# CV060_AO.net
KiCad netlist of a schematic drawn in Altium Designer
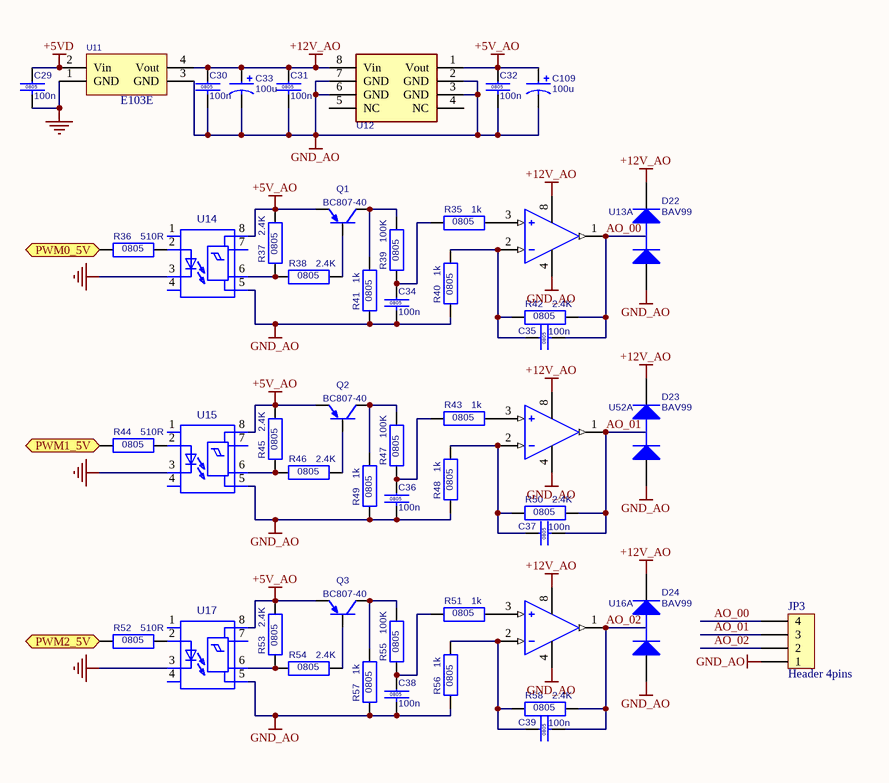
[diagram p0: CV060_AO.SchDoc]

(export (version "E")
  (design (tool "Eeschema 10.0.6"))
  (components
    (comp (ref "C29")
      (value "100n")
      (footprint "RC0805")
      (description "Chip capacitor, 20p")
      (fields
        (field (name "VOLTAGE") "50V")
        (field (name "MANUFACTURER") "KEMET, YAGEO")
        (field (name "CASE") "0805")
        (field (name "PUBLISHER") "ppavlov")
      )
      (libsource (lib "Aldiva_Altium_Library") (part "Capacitor_nonpolar_case"))
    )
    (comp (ref "C30")
      (value "100n")
      (footprint "RC0805")
      (description "Chip capacitor, 20p")
      (fields
        (field (name "VOLTAGE") "50V")
        (field (name "MANUFACTURER") "KEMET, YAGEO")
        (field (name "CASE") "0805")
        (field (name "PUBLISHER") "ppavlov")
      )
      (libsource (lib "Aldiva_Altium_Library") (part "Capacitor_nonpolar_case"))
    )
    (comp (ref "C31")
      (value "100n")
      (footprint "RC0805")
      (description "Chip capacitor, 20p")
      (fields
        (field (name "VOLTAGE") "50V")
        (field (name "MANUFACTURER") "KEMET, YAGEO")
        (field (name "CASE") "0805")
        (field (name "PUBLISHER") "ppavlov")
      )
      (libsource (lib "Aldiva_Altium_Library") (part "Capacitor_nonpolar_case"))
    )
    (comp (ref "C32")
      (value "100n")
      (footprint "RC0805")
      (description "Chip capacitor, 20p")
      (fields
        (field (name "VOLTAGE") "50V")
        (field (name "MANUFACTURER") "KEMET, YAGEO")
        (field (name "CASE") "0805")
        (field (name "PUBLISHER") "ppavlov")
      )
      (libsource (lib "Aldiva_Altium_Library") (part "Capacitor_nonpolar_case"))
    )
    (comp (ref "C33")
      (value "100u")
      (footprint "CEH12.5D5P2.5")
      (description "Electrolytic capacitor")
      (fields
        (field (name "PART NUMBER") "CEH12.5D5P2.5M-16V-100U")
        (field (name "VOLTAGE") "16V")
        (field (name "PUBLISHER") "ppavlov")
      )
      (libsource (lib "Aldiva_Altium_Library") (part "Capacitor_polar"))
    )
    (comp (ref "C34")
      (value "100n")
      (footprint "RC0805")
      (description "Chip capacitor, 20p")
      (fields
        (field (name "VOLTAGE") "50V")
        (field (name "MANUFACTURER") "KEMET, YAGEO")
        (field (name "CASE") "0805")
        (field (name "PUBLISHER") "ppavlov")
      )
      (libsource (lib "Aldiva_Altium_Library") (part "Capacitor_nonpolar_case"))
    )
    (comp (ref "C35")
      (value "100n")
      (footprint "RC0805")
      (description "Chip capacitor, 20p")
      (fields
        (field (name "VOLTAGE") "50V")
        (field (name "MANUFACTURER") "KEMET, YAGEO")
        (field (name "CASE") "0805")
        (field (name "PUBLISHER") "ppavlov")
      )
      (libsource (lib "Aldiva_Altium_Library") (part "Capacitor_nonpolar_case"))
    )
    (comp (ref "C36")
      (value "100n")
      (footprint "RC0805")
      (description "Chip capacitor, 20p")
      (fields
        (field (name "VOLTAGE") "50V")
        (field (name "MANUFACTURER") "KEMET, YAGEO")
        (field (name "CASE") "0805")
        (field (name "PUBLISHER") "ppavlov")
      )
      (libsource (lib "Aldiva_Altium_Library") (part "Capacitor_nonpolar_case"))
    )
    (comp (ref "C37")
      (value "100n")
      (footprint "RC0805")
      (description "Chip capacitor, 20p")
      (fields
        (field (name "VOLTAGE") "50V")
        (field (name "MANUFACTURER") "KEMET, YAGEO")
        (field (name "CASE") "0805")
        (field (name "PUBLISHER") "ppavlov")
      )
      (libsource (lib "Aldiva_Altium_Library") (part "Capacitor_nonpolar_case"))
    )
    (comp (ref "C38")
      (value "100n")
      (footprint "RC0805")
      (description "Chip capacitor, 20p")
      (fields
        (field (name "VOLTAGE") "50V")
        (field (name "MANUFACTURER") "KEMET, YAGEO")
        (field (name "CASE") "0805")
        (field (name "PUBLISHER") "ppavlov")
      )
      (libsource (lib "Aldiva_Altium_Library") (part "Capacitor_nonpolar_case"))
    )
    (comp (ref "C39")
      (value "100n")
      (footprint "RC0805")
      (description "Chip capacitor, 20p")
      (fields
        (field (name "VOLTAGE") "50V")
        (field (name "MANUFACTURER") "KEMET, YAGEO")
        (field (name "CASE") "0805")
        (field (name "PUBLISHER") "ppavlov")
      )
      (libsource (lib "Aldiva_Altium_Library") (part "Capacitor_nonpolar_case"))
    )
    (comp (ref "C109")
      (value "100u")
      (footprint "CEH12.5D5P2.5")
      (description "Electrolytic capacitor")
      (fields
        (field (name "PART NUMBER") "CEH12.5D5P2.5M-16V-100U")
        (field (name "VOLTAGE") "16V")
        (field (name "PUBLISHER") "ppavlov")
      )
      (libsource (lib "Aldiva_Altium_Library") (part "Capacitor_polar"))
    )
    (comp (ref "D22")
      (value "BAV99")
      (footprint "SOT23-3")
      (description "Dual small signal diode")
      (fields
        (field (name "MANUFACTURER") "Fairchild")
        (field (name "PART NUMBER") "BAV99")
        (field (name "VOLTAGE") "70V")
        (field (name "PUBLISHER") "tkondratyuk")
      )
      (libsource (lib "Aldiva_Altium_Library") (part "BAV99"))
    )
    (comp (ref "D23")
      (value "BAV99")
      (footprint "SOT23-3")
      (description "Dual small signal diode")
      (fields
        (field (name "MANUFACTURER") "Fairchild")
        (field (name "PART NUMBER") "BAV99")
        (field (name "VOLTAGE") "70V")
        (field (name "PUBLISHER") "tkondratyuk")
      )
      (libsource (lib "Aldiva_Altium_Library") (part "BAV99"))
    )
    (comp (ref "D24")
      (value "BAV99")
      (footprint "SOT23-3")
      (description "Dual small signal diode")
      (fields
        (field (name "MANUFACTURER") "Fairchild")
        (field (name "PART NUMBER") "BAV99")
        (field (name "VOLTAGE") "70V")
        (field (name "PUBLISHER") "tkondratyuk")
      )
      (libsource (lib "Aldiva_Altium_Library") (part "BAV99"))
    )
    (comp (ref "JP3")
      (value "Header 4pins")
      (footprint "PHOENIX_5.08_4PINS")
      (description "5.08mm angled 4pins receptabe")
      (fields
        (field (name "PART NUMBER") "2EDGR-5.08-04P-14")
        (field (name "MANUFACTURER PART NUMBER") "2EDGR-5.0-04P-14")
        (field (name "PUBLISHER") "ppavlov")
      )
      (libsource (lib "Aldiva_Altium_Library") (part "Header 4pins"))
    )
    (comp (ref "Q1")
      (value "PNP_transistor_SOT23-3")
      (footprint "SOT23-3")
      (description "General Purpose  PNP Transistor")
      (fields
        (field (name "PART NUMBER") "BC807-40")
        (field (name "MANUFACTURER") "ONS, NXP")
        (field (name "MANUFACTURER PART NUMBER") "BC807?40LT1G")
        (field (name "PUBLISHER") "tkondratyuk")
      )
      (libsource (lib "Aldiva_Altium_Library") (part "PNP_transistor_SOT23-3"))
    )
    (comp (ref "Q2")
      (value "PNP_transistor_SOT23-3")
      (footprint "SOT23-3")
      (description "General Purpose  PNP Transistor")
      (fields
        (field (name "PART NUMBER") "BC807-40")
        (field (name "MANUFACTURER") "ONS, NXP")
        (field (name "MANUFACTURER PART NUMBER") "BC807?40LT1G")
        (field (name "PUBLISHER") "tkondratyuk")
      )
      (libsource (lib "Aldiva_Altium_Library") (part "PNP_transistor_SOT23-3"))
    )
    (comp (ref "Q3")
      (value "PNP_transistor_SOT23-3")
      (footprint "SOT23-3")
      (description "General Purpose  PNP Transistor")
      (fields
        (field (name "PART NUMBER") "BC807-40")
        (field (name "MANUFACTURER") "ONS, NXP")
        (field (name "MANUFACTURER PART NUMBER") "BC807?40LT1G")
        (field (name "PUBLISHER") "tkondratyuk")
      )
      (libsource (lib "Aldiva_Altium_Library") (part "PNP_transistor_SOT23-3"))
    )
    (comp (ref "R35")
      (value "1k")
      (footprint "RC0805")
      (description "Chip resistor")
      (fields
        (field (name "CASE") "0805")
        (field (name "PART NUMBER") "RC0805F-1K00")
        (field (name "VOLTAGE") "200V")
        (field (name "PUBLISHER") "ppavlov")
      )
      (libsource (lib "Aldiva_Altium_Library") (part "Resistor"))
    )
    (comp (ref "R36")
      (value "510R")
      (footprint "RC0805")
      (description "Chip resistor")
      (fields
        (field (name "CASE") "0805")
        (field (name "PART NUMBER") "RC0805F-510R")
        (field (name "VOLTAGE") "200V")
        (field (name "PUBLISHER") "ppavlov")
      )
      (libsource (lib "Aldiva_Altium_Library") (part "Resistor"))
    )
    (comp (ref "R37")
      (value "2.4K")
      (footprint "RC0805")
      (description "Chip resistor")
      (fields
        (field (name "CASE") "0805")
        (field (name "PART NUMBER") "RC0805F-2K40")
        (field (name "VOLTAGE") "200V")
        (field (name "PUBLISHER") "ppavlov")
      )
      (libsource (lib "Aldiva_Altium_Library") (part "Resistor"))
    )
    (comp (ref "R38")
      (value "2.4K")
      (footprint "RC0805")
      (description "Chip resistor")
      (fields
        (field (name "CASE") "0805")
        (field (name "PART NUMBER") "RC0805F-2K40")
        (field (name "VOLTAGE") "200V")
        (field (name "PUBLISHER") "ppavlov")
      )
      (libsource (lib "Aldiva_Altium_Library") (part "Resistor"))
    )
    (comp (ref "R39")
      (value "100K")
      (footprint "RC0805")
      (description "Chip resistor")
      (fields
        (field (name "CASE") "0805")
        (field (name "PART NUMBER") "RC0805F-100K")
        (field (name "VOLTAGE") "200V")
        (field (name "PUBLISHER") "ppavlov")
      )
      (libsource (lib "Aldiva_Altium_Library") (part "Resistor"))
    )
    (comp (ref "R40")
      (value "1k")
      (footprint "RC0805")
      (description "Chip resistor")
      (fields
        (field (name "CASE") "0805")
        (field (name "PART NUMBER") "RC0805F-1K00")
        (field (name "VOLTAGE") "200V")
        (field (name "PUBLISHER") "ppavlov")
      )
      (libsource (lib "Aldiva_Altium_Library") (part "Resistor"))
    )
    (comp (ref "R41")
      (value "1k")
      (footprint "RC0805")
      (description "Chip resistor")
      (fields
        (field (name "CASE") "0805")
        (field (name "PART NUMBER") "RC0805F-1K00")
        (field (name "VOLTAGE") "200V")
        (field (name "PUBLISHER") "ppavlov")
      )
      (libsource (lib "Aldiva_Altium_Library") (part "Resistor"))
    )
    (comp (ref "R42")
      (value "2.4K")
      (footprint "RC0805")
      (description "Chip resistor")
      (fields
        (field (name "CASE") "0805")
        (field (name "PART NUMBER") "RC0805F-2K40")
        (field (name "VOLTAGE") "200V")
        (field (name "PUBLISHER") "ppavlov")
      )
      (libsource (lib "Aldiva_Altium_Library") (part "Resistor"))
    )
    (comp (ref "R43")
      (value "1k")
      (footprint "RC0805")
      (description "Chip resistor")
      (fields
        (field (name "CASE") "0805")
        (field (name "PART NUMBER") "RC0805F-1K00")
        (field (name "VOLTAGE") "200V")
        (field (name "PUBLISHER") "ppavlov")
      )
      (libsource (lib "Aldiva_Altium_Library") (part "Resistor"))
    )
    (comp (ref "R44")
      (value "510R")
      (footprint "RC0805")
      (description "Chip resistor")
      (fields
        (field (name "CASE") "0805")
        (field (name "PART NUMBER") "RC0805F-510R")
        (field (name "VOLTAGE") "200V")
        (field (name "PUBLISHER") "ppavlov")
      )
      (libsource (lib "Aldiva_Altium_Library") (part "Resistor"))
    )
    (comp (ref "R45")
      (value "2.4K")
      (footprint "RC0805")
      (description "Chip resistor")
      (fields
        (field (name "CASE") "0805")
        (field (name "PART NUMBER") "RC0805F-2K40")
        (field (name "VOLTAGE") "200V")
        (field (name "PUBLISHER") "ppavlov")
      )
      (libsource (lib "Aldiva_Altium_Library") (part "Resistor"))
    )
    (comp (ref "R46")
      (value "2.4K")
      (footprint "RC0805")
      (description "Chip resistor")
      (fields
        (field (name "CASE") "0805")
        (field (name "PART NUMBER") "RC0805F-2K40")
        (field (name "VOLTAGE") "200V")
        (field (name "PUBLISHER") "ppavlov")
      )
      (libsource (lib "Aldiva_Altium_Library") (part "Resistor"))
    )
    (comp (ref "R47")
      (value "100K")
      (footprint "RC0805")
      (description "Chip resistor")
      (fields
        (field (name "CASE") "0805")
        (field (name "PART NUMBER") "RC0805F-100K")
        (field (name "VOLTAGE") "200V")
        (field (name "PUBLISHER") "ppavlov")
      )
      (libsource (lib "Aldiva_Altium_Library") (part "Resistor"))
    )
    (comp (ref "R48")
      (value "1k")
      (footprint "RC0805")
      (description "Chip resistor")
      (fields
        (field (name "CASE") "0805")
        (field (name "PART NUMBER") "RC0805F-1K00")
        (field (name "VOLTAGE") "200V")
        (field (name "PUBLISHER") "ppavlov")
      )
      (libsource (lib "Aldiva_Altium_Library") (part "Resistor"))
    )
    (comp (ref "R49")
      (value "1k")
      (footprint "RC0805")
      (description "Chip resistor")
      (fields
        (field (name "CASE") "0805")
        (field (name "PART NUMBER") "RC0805F-1K00")
        (field (name "VOLTAGE") "200V")
        (field (name "PUBLISHER") "ppavlov")
      )
      (libsource (lib "Aldiva_Altium_Library") (part "Resistor"))
    )
    (comp (ref "R50")
      (value "2.4K")
      (footprint "RC0805")
      (description "Chip resistor")
      (fields
        (field (name "CASE") "0805")
        (field (name "PART NUMBER") "RC0805F-2K40")
        (field (name "VOLTAGE") "200V")
        (field (name "PUBLISHER") "ppavlov")
      )
      (libsource (lib "Aldiva_Altium_Library") (part "Resistor"))
    )
    (comp (ref "R51")
      (value "1k")
      (footprint "RC0805")
      (description "Chip resistor")
      (fields
        (field (name "CASE") "0805")
        (field (name "PART NUMBER") "RC0805F-1K00")
        (field (name "VOLTAGE") "200V")
        (field (name "PUBLISHER") "ppavlov")
      )
      (libsource (lib "Aldiva_Altium_Library") (part "Resistor"))
    )
    (comp (ref "R52")
      (value "510R")
      (footprint "RC0805")
      (description "Chip resistor")
      (fields
        (field (name "CASE") "0805")
        (field (name "PART NUMBER") "RC0805F-510R")
        (field (name "VOLTAGE") "200V")
        (field (name "PUBLISHER") "ppavlov")
      )
      (libsource (lib "Aldiva_Altium_Library") (part "Resistor"))
    )
    (comp (ref "R53")
      (value "2.4K")
      (footprint "RC0805")
      (description "Chip resistor")
      (fields
        (field (name "CASE") "0805")
        (field (name "PART NUMBER") "RC0805F-2K40")
        (field (name "VOLTAGE") "200V")
        (field (name "PUBLISHER") "ppavlov")
      )
      (libsource (lib "Aldiva_Altium_Library") (part "Resistor"))
    )
    (comp (ref "R54")
      (value "2.4K")
      (footprint "RC0805")
      (description "Chip resistor")
      (fields
        (field (name "CASE") "0805")
        (field (name "PART NUMBER") "RC0805F-2K40")
        (field (name "VOLTAGE") "200V")
        (field (name "PUBLISHER") "ppavlov")
      )
      (libsource (lib "Aldiva_Altium_Library") (part "Resistor"))
    )
    (comp (ref "R55")
      (value "100K")
      (footprint "RC0805")
      (description "Chip resistor")
      (fields
        (field (name "CASE") "0805")
        (field (name "PART NUMBER") "RC0805F-100K")
        (field (name "VOLTAGE") "200V")
        (field (name "PUBLISHER") "ppavlov")
      )
      (libsource (lib "Aldiva_Altium_Library") (part "Resistor"))
    )
    (comp (ref "R56")
      (value "1k")
      (footprint "RC0805")
      (description "Chip resistor")
      (fields
        (field (name "CASE") "0805")
        (field (name "PART NUMBER") "RC0805F-1K00")
        (field (name "VOLTAGE") "200V")
        (field (name "PUBLISHER") "ppavlov")
      )
      (libsource (lib "Aldiva_Altium_Library") (part "Resistor"))
    )
    (comp (ref "R57")
      (value "1k")
      (footprint "RC0805")
      (description "Chip resistor")
      (fields
        (field (name "CASE") "0805")
        (field (name "PART NUMBER") "RC0805F-1K00")
        (field (name "VOLTAGE") "200V")
        (field (name "PUBLISHER") "ppavlov")
      )
      (libsource (lib "Aldiva_Altium_Library") (part "Resistor"))
    )
    (comp (ref "R58")
      (value "2.4K")
      (footprint "RC0805")
      (description "Chip resistor")
      (fields
        (field (name "CASE") "0805")
        (field (name "PART NUMBER") "RC0805F-2K40")
        (field (name "VOLTAGE") "200V")
        (field (name "PUBLISHER") "ppavlov")
      )
      (libsource (lib "Aldiva_Altium_Library") (part "Resistor"))
    )
    (comp (ref "U11")
      (value "~")
      (footprint "SIP4")
      (description "1W Insulated DCDC converter 5 to 12V")
      (fields
        (field (name "PART NUMBER") "1-05-12S")
        (field (name "MANUFACTURER") "TI")
        (field (name "MANUFACTURER PART NUMBER") "E103E")
        (field (name "PUBLISHER") "ppavlov")
      )
      (libsource (lib "Aldiva_Altium_Library") (part "DCDC"))
    )
    (comp (ref "U12")
      (value "L78L05CD")
      (footprint "SO-8")
      (description "Regulator 100ma 5V")
      (fields (field (name "MANUFACTURER") "ST") (field (name "PUBLISHER") "ppavlov"))
      (libsource (lib "Aldiva_Altium_Library") (part "78L05"))
    )
    (comp (ref "U13")
      (value "LM2904D")
      (footprint "SO-8")
      (description "Dual opamps")
      (fields (field (name "MANUFACTURER") "TI") (field (name "PUBLISHER") "tkondratyuk"))
      (libsource (lib "Aldiva_Altium_Library") (part "LM2904D"))
    )
    (comp (ref "U14")
      (value "6N137")
      (footprint "DIP8")
      (description "High CMR, High Speed TTL\r\nCompatible Optocouplers")
      (fields (field (name "PUBLISHER") "ppavlov"))
      (libsource (lib "Aldiva_Altium_Library") (part "6N137"))
    )
    (comp (ref "U15")
      (value "6N137")
      (footprint "DIP8")
      (description "High CMR, High Speed TTL\r\nCompatible Optocouplers")
      (fields (field (name "PUBLISHER") "ppavlov"))
      (libsource (lib "Aldiva_Altium_Library") (part "6N137"))
    )
    (comp (ref "U16")
      (value "LM2904D")
      (footprint "SO-8")
      (description "Dual opamps")
      (fields (field (name "MANUFACTURER") "TI") (field (name "PUBLISHER") "tkondratyuk"))
      (libsource (lib "Aldiva_Altium_Library") (part "LM2904D"))
    )
    (comp (ref "U17")
      (value "6N137")
      (footprint "DIP8")
      (description "High CMR, High Speed TTL\r\nCompatible Optocouplers")
      (fields (field (name "PUBLISHER") "ppavlov"))
      (libsource (lib "Aldiva_Altium_Library") (part "6N137"))
    )
    (comp (ref "U52")
      (value "LM2904D")
      (footprint "SO-8")
      (description "Dual opamps")
      (fields (field (name "MANUFACTURER") "TI") (field (name "PUBLISHER") "tkondratyuk"))
      (libsource (lib "Aldiva_Altium_Library") (part "LM2904D"))
    )
  )
  (nets
    (net (code "1") (name "+5VD") (class "Default")
      (node (ref "C29") (pin "1") (pinfunction "1_1") (pintype "passive"))
      (node (ref "U11") (pin "2") (pinfunction "Vin_2") (pintype "passive"))
    )
    (net (code "2") (name "+5V_AO") (class "Default")
      (node (ref "C109") (pin "1") (pinfunction "1_1") (pintype "passive"))
      (node (ref "C32") (pin "1") (pinfunction "1_1") (pintype "passive"))
      (node (ref "Q1") (pin "2") (pinfunction "E_2") (pintype "passive"))
      (node (ref "Q2") (pin "2") (pinfunction "E_2") (pintype "passive"))
      (node (ref "Q3") (pin "2") (pinfunction "E_2") (pintype "passive"))
      (node (ref "R37") (pin "2") (pinfunction "2_2") (pintype "passive"))
      (node (ref "R45") (pin "2") (pinfunction "2_2") (pintype "passive"))
      (node (ref "R53") (pin "2") (pinfunction "2_2") (pintype "passive"))
      (node (ref "U12") (pin "1") (pinfunction "Vout_1") (pintype "passive"))
      (node (ref "U14") (pin "8") (pintype "passive"))
      (node (ref "U15") (pin "8") (pintype "passive"))
      (node (ref "U17") (pin "8") (pintype "passive"))
    )
    (net (code "3") (name "+12V_AO") (class "Default")
      (node (ref "C30") (pin "1") (pinfunction "1_1") (pintype "passive"))
      (node (ref "C31") (pin "1") (pinfunction "1_1") (pintype "passive"))
      (node (ref "C33") (pin "1") (pinfunction "1_1") (pintype "passive"))
      (node (ref "D22") (pin "2") (pinfunction "K_2") (pintype "passive"))
      (node (ref "D23") (pin "2") (pinfunction "K_2") (pintype "passive"))
      (node (ref "D24") (pin "2") (pinfunction "K_2") (pintype "passive"))
      (node (ref "U11") (pin "4") (pinfunction "Vout_4") (pintype "passive"))
      (node (ref "U12") (pin "8") (pinfunction "Vin_8") (pintype "passive"))
      (node (ref "U13") (pin "8") (pinfunction "Vcc+_8") (pintype "power_in"))
      (node (ref "U16") (pin "8") (pinfunction "Vcc+_8") (pintype "power_in"))
      (node (ref "U52") (pin "8") (pinfunction "Vcc+_8") (pintype "power_in"))
    )
    (net (code "4") (name "/AO_00") (class "Default")
      (node (ref "C35") (pin "2") (pinfunction "2_2") (pintype "passive"))
      (node (ref "D22") (pin "3") (pinfunction "C_3") (pintype "passive"))
      (node (ref "JP3") (pin "4") (pinfunction "4_4") (pintype "passive"))
      (node (ref "R42") (pin "2") (pinfunction "2_2") (pintype "passive"))
      (node (ref "U13") (pin "1") (pinfunction "OUT1_1") (pintype "output"))
    )
    (net (code "5") (name "/AO_01") (class "Default")
      (node (ref "C37") (pin "2") (pinfunction "2_2") (pintype "passive"))
      (node (ref "D23") (pin "3") (pinfunction "C_3") (pintype "passive"))
      (node (ref "JP3") (pin "3") (pinfunction "3_3") (pintype "passive"))
      (node (ref "R50") (pin "2") (pinfunction "2_2") (pintype "passive"))
      (node (ref "U52") (pin "1") (pinfunction "OUT1_1") (pintype "output"))
    )
    (net (code "6") (name "/AO_02") (class "Default")
      (node (ref "C39") (pin "2") (pinfunction "2_2") (pintype "passive"))
      (node (ref "D24") (pin "3") (pinfunction "C_3") (pintype "passive"))
      (node (ref "JP3") (pin "2") (pinfunction "2_2") (pintype "passive"))
      (node (ref "R58") (pin "2") (pinfunction "2_2") (pintype "passive"))
      (node (ref "U16") (pin "1") (pinfunction "OUT1_1") (pintype "output"))
    )
    (net (code "7") (name "/PWM0_5V") (class "Default")
      (node (ref "R36") (pin "1") (pinfunction "1_1") (pintype "passive"))
    )
    (net (code "8") (name "/PWM1_5V") (class "Default")
      (node (ref "R44") (pin "1") (pinfunction "1_1") (pintype "passive"))
    )
    (net (code "9") (name "/PWM2_5V") (class "Default")
      (node (ref "R52") (pin "1") (pinfunction "1_1") (pintype "passive"))
    )
    (net (code "10") (name "DGND") (class "Default")
      (node (ref "C29") (pin "2") (pinfunction "2_2") (pintype "passive"))
      (node (ref "U11") (pin "1") (pinfunction "GND_1") (pintype "passive"))
      (node (ref "U14") (pin "3") (pintype "passive"))
      (node (ref "U15") (pin "3") (pintype "passive"))
      (node (ref "U17") (pin "3") (pintype "passive"))
    )
    (net (code "11") (name "GND_AO") (class "Default")
      (node (ref "C109") (pin "2") (pinfunction "2_2") (pintype "passive"))
      (node (ref "C30") (pin "2") (pinfunction "2_2") (pintype "passive"))
      (node (ref "C31") (pin "2") (pinfunction "2_2") (pintype "passive"))
      (node (ref "C32") (pin "2") (pinfunction "2_2") (pintype "passive"))
      (node (ref "C33") (pin "2") (pinfunction "2_2") (pintype "passive"))
      (node (ref "C34") (pin "2") (pinfunction "2_2") (pintype "passive"))
      (node (ref "C36") (pin "2") (pinfunction "2_2") (pintype "passive"))
      (node (ref "C38") (pin "2") (pinfunction "2_2") (pintype "passive"))
      (node (ref "D22") (pin "1") (pinfunction "A_1") (pintype "passive"))
      (node (ref "D23") (pin "1") (pinfunction "A_1") (pintype "passive"))
      (node (ref "D24") (pin "1") (pinfunction "A_1") (pintype "passive"))
      (node (ref "JP3") (pin "1") (pinfunction "1_1") (pintype "passive"))
      (node (ref "R40") (pin "1") (pinfunction "1_1") (pintype "passive"))
      (node (ref "R41") (pin "1") (pinfunction "1_1") (pintype "passive"))
      (node (ref "R48") (pin "1") (pinfunction "1_1") (pintype "passive"))
      (node (ref "R49") (pin "1") (pinfunction "1_1") (pintype "passive"))
      (node (ref "R56") (pin "1") (pinfunction "1_1") (pintype "passive"))
      (node (ref "R57") (pin "1") (pinfunction "1_1") (pintype "passive"))
      (node (ref "U11") (pin "3") (pinfunction "GND_3") (pintype "passive"))
      (node (ref "U12") (pin "2") (pinfunction "GND_2") (pintype "passive"))
      (node (ref "U12") (pin "3") (pinfunction "GND_3") (pintype "passive"))
      (node (ref "U12") (pin "6") (pinfunction "GND_6") (pintype "passive"))
      (node (ref "U12") (pin "7") (pinfunction "GND_7") (pintype "passive"))
      (node (ref "U13") (pin "4") (pinfunction "Vcc-_4") (pintype "power_in"))
      (node (ref "U14") (pin "5") (pintype "passive"))
      (node (ref "U15") (pin "5") (pintype "passive"))
      (node (ref "U16") (pin "4") (pinfunction "Vcc-_4") (pintype "power_in"))
      (node (ref "U17") (pin "5") (pintype "passive"))
      (node (ref "U52") (pin "4") (pinfunction "Vcc-_4") (pintype "power_in"))
    )
    (net (code "12") (name "Net-(C34-Pad1)") (class "Default")
      (node (ref "C34") (pin "1") (pinfunction "1_1") (pintype "passive"))
      (node (ref "R35") (pin "1") (pinfunction "1_1") (pintype "passive"))
      (node (ref "R39") (pin "1") (pinfunction "1_1") (pintype "passive"))
    )
    (net (code "13") (name "Net-(C36-Pad1)") (class "Default")
      (node (ref "C36") (pin "1") (pinfunction "1_1") (pintype "passive"))
      (node (ref "R43") (pin "1") (pinfunction "1_1") (pintype "passive"))
      (node (ref "R47") (pin "1") (pinfunction "1_1") (pintype "passive"))
    )
    (net (code "14") (name "Net-(C38-Pad1)") (class "Default")
      (node (ref "C38") (pin "1") (pinfunction "1_1") (pintype "passive"))
      (node (ref "R51") (pin "1") (pinfunction "1_1") (pintype "passive"))
      (node (ref "R55") (pin "1") (pinfunction "1_1") (pintype "passive"))
    )
    (net (code "15") (name "Net-(Q1-B)") (class "Default")
      (node (ref "Q1") (pin "1") (pinfunction "B_1") (pintype "passive"))
      (node (ref "R38") (pin "2") (pinfunction "2_2") (pintype "passive"))
    )
    (net (code "16") (name "Net-(Q1-C)") (class "Default")
      (node (ref "Q1") (pin "3") (pinfunction "C_3") (pintype "passive"))
      (node (ref "R39") (pin "2") (pinfunction "2_2") (pintype "passive"))
      (node (ref "R41") (pin "2") (pinfunction "2_2") (pintype "passive"))
    )
    (net (code "17") (name "Net-(Q2-B)") (class "Default")
      (node (ref "Q2") (pin "1") (pinfunction "B_1") (pintype "passive"))
      (node (ref "R46") (pin "2") (pinfunction "2_2") (pintype "passive"))
    )
    (net (code "18") (name "Net-(Q2-C)") (class "Default")
      (node (ref "Q2") (pin "3") (pinfunction "C_3") (pintype "passive"))
      (node (ref "R47") (pin "2") (pinfunction "2_2") (pintype "passive"))
      (node (ref "R49") (pin "2") (pinfunction "2_2") (pintype "passive"))
    )
    (net (code "19") (name "Net-(Q3-B)") (class "Default")
      (node (ref "Q3") (pin "1") (pinfunction "B_1") (pintype "passive"))
      (node (ref "R54") (pin "2") (pinfunction "2_2") (pintype "passive"))
    )
    (net (code "20") (name "Net-(Q3-C)") (class "Default")
      (node (ref "Q3") (pin "3") (pinfunction "C_3") (pintype "passive"))
      (node (ref "R55") (pin "2") (pinfunction "2_2") (pintype "passive"))
      (node (ref "R57") (pin "2") (pinfunction "2_2") (pintype "passive"))
    )
    (net (code "21") (name "Net-(R36-Pad2)") (class "Default")
      (node (ref "R36") (pin "2") (pinfunction "2_2") (pintype "passive"))
      (node (ref "U14") (pin "2") (pintype "passive"))
    )
    (net (code "22") (name "Net-(R37-Pad1)") (class "Default")
      (node (ref "R37") (pin "1") (pinfunction "1_1") (pintype "passive"))
      (node (ref "R38") (pin "1") (pinfunction "1_1") (pintype "passive"))
      (node (ref "U14") (pin "6") (pintype "passive"))
    )
    (net (code "23") (name "Net-(R44-Pad2)") (class "Default")
      (node (ref "R44") (pin "2") (pinfunction "2_2") (pintype "passive"))
      (node (ref "U15") (pin "2") (pintype "passive"))
    )
    (net (code "24") (name "Net-(R45-Pad1)") (class "Default")
      (node (ref "R45") (pin "1") (pinfunction "1_1") (pintype "passive"))
      (node (ref "R46") (pin "1") (pinfunction "1_1") (pintype "passive"))
      (node (ref "U15") (pin "6") (pintype "passive"))
    )
    (net (code "25") (name "Net-(R52-Pad2)") (class "Default")
      (node (ref "R52") (pin "2") (pinfunction "2_2") (pintype "passive"))
      (node (ref "U17") (pin "2") (pintype "passive"))
    )
    (net (code "26") (name "Net-(R53-Pad1)") (class "Default")
      (node (ref "R53") (pin "1") (pinfunction "1_1") (pintype "passive"))
      (node (ref "R54") (pin "1") (pinfunction "1_1") (pintype "passive"))
      (node (ref "U17") (pin "6") (pintype "passive"))
    )
    (net (code "27") (name "Net-(U13A-IN1+)") (class "Default")
      (node (ref "R35") (pin "2") (pinfunction "2_2") (pintype "passive"))
      (node (ref "U13") (pin "3") (pinfunction "IN1+_3") (pintype "input"))
    )
    (net (code "28") (name "Net-(U13A-IN1-)") (class "Default")
      (node (ref "C35") (pin "1") (pinfunction "1_1") (pintype "passive"))
      (node (ref "R40") (pin "2") (pinfunction "2_2") (pintype "passive"))
      (node (ref "R42") (pin "1") (pinfunction "1_1") (pintype "passive"))
      (node (ref "U13") (pin "2") (pinfunction "IN1-_2") (pintype "input"))
    )
    (net (code "29") (name "Net-(U16A-IN1+)") (class "Default")
      (node (ref "R51") (pin "2") (pinfunction "2_2") (pintype "passive"))
      (node (ref "U16") (pin "3") (pinfunction "IN1+_3") (pintype "input"))
    )
    (net (code "30") (name "Net-(U16A-IN1-)") (class "Default")
      (node (ref "C39") (pin "1") (pinfunction "1_1") (pintype "passive"))
      (node (ref "R56") (pin "2") (pinfunction "2_2") (pintype "passive"))
      (node (ref "R58") (pin "1") (pinfunction "1_1") (pintype "passive"))
      (node (ref "U16") (pin "2") (pinfunction "IN1-_2") (pintype "input"))
    )
    (net (code "31") (name "Net-(U52A-IN1+)") (class "Default")
      (node (ref "R43") (pin "2") (pinfunction "2_2") (pintype "passive"))
      (node (ref "U52") (pin "3") (pinfunction "IN1+_3") (pintype "input"))
    )
    (net (code "32") (name "Net-(U52A-IN1-)") (class "Default")
      (node (ref "C37") (pin "1") (pinfunction "1_1") (pintype "passive"))
      (node (ref "R48") (pin "2") (pinfunction "2_2") (pintype "passive"))
      (node (ref "R50") (pin "1") (pinfunction "1_1") (pintype "passive"))
      (node (ref "U52") (pin "2") (pinfunction "IN1-_2") (pintype "input"))
    )
    (net (code "33") (name "unconnected-(U12-NC-Pad4)") (class "Default")
      (node (ref "U12") (pin "4") (pinfunction "NC_4") (pintype "passive"))
    )
    (net (code "34") (name "unconnected-(U12-NC-Pad5)") (class "Default")
      (node (ref "U12") (pin "5") (pinfunction "NC_5") (pintype "passive"))
    )
    (net (code "35") (name "unconnected-(U14-Pad1)") (class "Default")
      (node (ref "U14") (pin "1") (pintype "passive"))
    )
    (net (code "36") (name "unconnected-(U14-Pad4)") (class "Default")
      (node (ref "U14") (pin "4") (pintype "passive"))
    )
    (net (code "37") (name "unconnected-(U14-Pad7)") (class "Default")
      (node (ref "U14") (pin "7") (pintype "passive"))
    )
    (net (code "38") (name "unconnected-(U15-Pad1)") (class "Default")
      (node (ref "U15") (pin "1") (pintype "passive"))
    )
    (net (code "39") (name "unconnected-(U15-Pad4)") (class "Default")
      (node (ref "U15") (pin "4") (pintype "passive"))
    )
    (net (code "40") (name "unconnected-(U15-Pad7)") (class "Default")
      (node (ref "U15") (pin "7") (pintype "passive"))
    )
    (net (code "41") (name "unconnected-(U17-Pad1)") (class "Default")
      (node (ref "U17") (pin "1") (pintype "passive"))
    )
    (net (code "42") (name "unconnected-(U17-Pad4)") (class "Default")
      (node (ref "U17") (pin "4") (pintype "passive"))
    )
    (net (code "43") (name "unconnected-(U17-Pad7)") (class "Default")
      (node (ref "U17") (pin "7") (pintype "passive"))
    )
  )
)
